# v1_1.net
KiCad netlist of a schematic drawn in Altium Designer
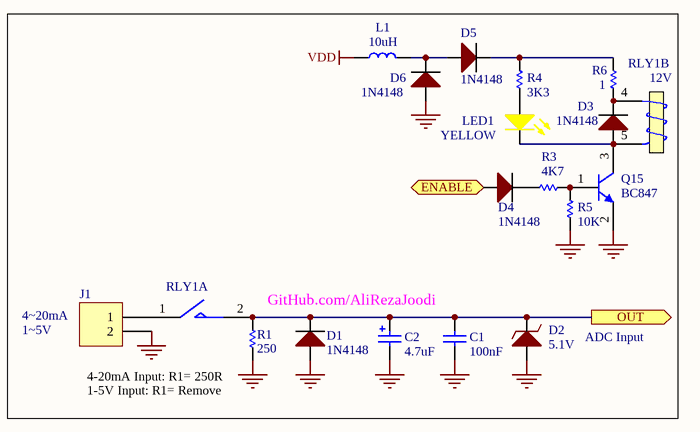
[diagram p0: v1.1.SchDoc]

(export (version "E")
  (design (tool "Eeschema 10.0.6"))
  (components
    (comp (ref "C1")
      (value "100nF")
      (footprint "CAPNTO2.54-3.05x1.78A")
      (description "Capacitor")
      (fields (field (name "MANUFACTURER") "Generic Components") (field (name "PUBLISHER") "Altium Limited"))
      (libsource (lib "Miscellaneous Devices") (part "Cap"))
    )
    (comp (ref "C2")
      (value "4.7uF")
      (footprint "CAPPR2.5-6.3x5")
      (description "Polarized Capacitor (Radial)")
      (fields (field (name "MANUFACTURER") "Generic Components") (field (name "PUBLISHER") "Altium Limited"))
      (libsource (lib "Miscellaneous Devices") (part "Cap Pol1"))
    )
    (comp (ref "D1")
      (value "1N4148")
      (footprint "D_THD_AXIAL0.3_DO-35")
      (description "Diode,")
      (libsource (lib "Passive") (part "Diode_2Form"))
    )
    (comp (ref "D2")
      (value "5.1V")
      (footprint "D_THD_AXIAL0.3_DO-35")
      (description "Diode, Zener")
      (libsource (lib "Passive") (part "Diode_Zener"))
    )
    (comp (ref "D3")
      (value "1N4148")
      (footprint "D_THD_AXIAL0.3_DO-35")
      (description "Diode,")
      (libsource (lib "Passive") (part "Diode_2Form"))
    )
    (comp (ref "D4")
      (value "1N4148")
      (footprint "D_THD_AXIAL0.3_DO-35")
      (description "Diode,")
      (libsource (lib "Passive") (part "Diode_2Form"))
    )
    (comp (ref "D5")
      (value "1N4148")
      (footprint "D_THD_AXIAL0.3_DO-35")
      (description "Diode,")
      (libsource (lib "Passive") (part "Diode_2Form"))
    )
    (comp (ref "D6")
      (value "1N4148")
      (footprint "D_THD_AXIAL0.3_DO-35")
      (description "Diode,")
      (libsource (lib "Passive") (part "Diode_2Form"))
    )
    (comp (ref "J1")
      (value "Header 2")
      (footprint "Fonics_2PIN_1")
      (description "Header, 2-Pin")
      (fields (field (name "PUBLISHER") "Altium Limited"))
      (libsource (lib "Miscellaneous Connectors") (part "Header 2"))
    )
    (comp (ref "L1")
      (value "10uH")
      (description "Inductor,")
      (libsource (lib "Passive") (part "Inductor_2Type"))
    )
    (comp (ref "LED1")
      (value "YELLOW")
      (footprint "LED_THD_3MM_YELLOW_R")
      (description "LED, Yellow")
      (fields (field (name "MANUFACTURER") "Generic Components") (field (name "PUBLISHER") "Altium Limited"))
      (libsource (lib "Display") (part "LED_YELLOW"))
    )
    (comp (ref "Q1")
      (value "Q15")
      (footprint "SOT23-3N")
      (description "Silicon Bipolar Transistor")
      (fields (field (name "ALTIUM_VALUE") "BC847"))
      (libsource (lib "my Libraries") (part "BC847"))
    )
    (comp (ref "R1")
      (value "250")
      (footprint "R_THD_AXIAL0.4(1/4W)")
      (description "Resistor")
      (libsource (lib "Passive") (part "Resistor"))
    )
    (comp (ref "R3")
      (value "4K7")
      (footprint "R_THD_AXIAL0.4(1/4W)")
      (description "Resistor")
      (libsource (lib "Passive") (part "Resistor"))
    )
    (comp (ref "R4")
      (value "3K3")
      (footprint "R_THD_AXIAL0.4(1/4W)")
      (description "Resistor")
      (libsource (lib "Passive") (part "Resistor"))
    )
    (comp (ref "R5")
      (value "10K")
      (footprint "R_THD_AXIAL0.4(1/4W)")
      (description "Resistor")
      (libsource (lib "Passive") (part "Resistor"))
    )
    (comp (ref "R6")
      (value "1")
      (footprint "R_THD_AXIAL0.4(1/4W)")
      (description "Resistor")
      (libsource (lib "Passive") (part "Resistor"))
    )
    (comp (ref "RLY1")
      (value "RELAU")
      (footprint "RELAY-SPDT-2")
      (fields (field (name "PUBLISHER") "Altium Limited"))
      (libsource (lib "my Libraries") (part "RELAY-NY12W-K"))
    )
  )
  (nets
    (net (code "1") (name "/ENABLE") (class "Default")
      (node (ref "D4") (pin "1") (pinfunction "A_1") (pintype "passive"))
    )
    (net (code "2") (name "/OUT") (class "Default")
      (node (ref "C1") (pin "2") (pinfunction "2_2") (pintype "passive"))
      (node (ref "C2") (pin "1") (pinfunction "1_1") (pintype "passive"))
      (node (ref "D1") (pin "2") (pinfunction "K_2") (pintype "passive"))
      (node (ref "D2") (pin "2") (pinfunction "2_2") (pintype "passive"))
      (node (ref "R1") (pin "1") (pinfunction "1_1") (pintype "passive"))
      (node (ref "RLY1") (pin "2") (pinfunction "NO_2") (pintype "passive"))
    )
    (net (code "3") (name "GND") (class "Default")
      (node (ref "C1") (pin "1") (pinfunction "1_1") (pintype "passive"))
      (node (ref "C2") (pin "2") (pinfunction "2_2") (pintype "passive"))
      (node (ref "D1") (pin "1") (pinfunction "A_1") (pintype "passive"))
      (node (ref "D2") (pin "1") (pinfunction "1_1") (pintype "passive"))
      (node (ref "D6") (pin "1") (pinfunction "A_1") (pintype "passive"))
      (node (ref "J1") (pin "2") (pinfunction "2_2") (pintype "passive"))
      (node (ref "Q1") (pin "2") (pinfunction "E_2") (pintype "passive"))
      (node (ref "R1") (pin "2") (pinfunction "2_2") (pintype "passive"))
      (node (ref "R5") (pin "1") (pinfunction "1_1") (pintype "passive"))
    )
    (net (code "4") (name "Net-(D3-A)") (class "Default")
      (node (ref "D3") (pin "1") (pinfunction "A_1") (pintype "passive"))
      (node (ref "LED1") (pin "2") (pinfunction "K_2") (pintype "passive"))
      (node (ref "Q1") (pin "3") (pinfunction "C_3") (pintype "passive"))
      (node (ref "RLY1") (pin "5") (pinfunction "T2_5") (pintype "passive"))
    )
    (net (code "5") (name "Net-(D3-K)") (class "Default")
      (node (ref "D3") (pin "2") (pinfunction "K_2") (pintype "passive"))
      (node (ref "R6") (pin "2") (pinfunction "2_2") (pintype "passive"))
      (node (ref "RLY1") (pin "4") (pinfunction "T1_4") (pintype "passive"))
    )
    (net (code "6") (name "Net-(D4-K)") (class "Default")
      (node (ref "D4") (pin "2") (pinfunction "K_2") (pintype "passive"))
      (node (ref "R3") (pin "2") (pinfunction "2_2") (pintype "passive"))
    )
    (net (code "7") (name "Net-(D5-A)") (class "Default")
      (node (ref "D5") (pin "1") (pinfunction "A_1") (pintype "passive"))
      (node (ref "D6") (pin "2") (pinfunction "K_2") (pintype "passive"))
      (node (ref "L1") (pin "2") (pinfunction "2_2") (pintype "passive"))
    )
    (net (code "8") (name "Net-(D5-K)") (class "Default")
      (node (ref "D5") (pin "2") (pinfunction "K_2") (pintype "passive"))
      (node (ref "R4") (pin "2") (pinfunction "2_2") (pintype "passive"))
      (node (ref "R6") (pin "1") (pinfunction "1_1") (pintype "passive"))
    )
    (net (code "9") (name "Net-(LED1-A)") (class "Default")
      (node (ref "LED1") (pin "1") (pinfunction "A_1") (pintype "passive"))
      (node (ref "R4") (pin "1") (pinfunction "1_1") (pintype "passive"))
    )
    (net (code "10") (name "Net-(Q1-B)") (class "Default")
      (node (ref "Q1") (pin "1") (pinfunction "B_1") (pintype "passive"))
      (node (ref "R3") (pin "1") (pinfunction "1_1") (pintype "passive"))
      (node (ref "R5") (pin "2") (pinfunction "2_2") (pintype "passive"))
    )
    (net (code "11") (name "Net-(RLY1A-COM)") (class "Default")
      (node (ref "J1") (pin "1") (pinfunction "1_1") (pintype "passive"))
      (node (ref "RLY1") (pin "1") (pinfunction "COM_1") (pintype "passive"))
    )
    (net (code "12") (name "VDD") (class "Default")
      (node (ref "L1") (pin "1") (pinfunction "1_1") (pintype "passive"))
    )
  )
)
